# LM471.net
KiCad netlist of a schematic drawn in EasyEDA
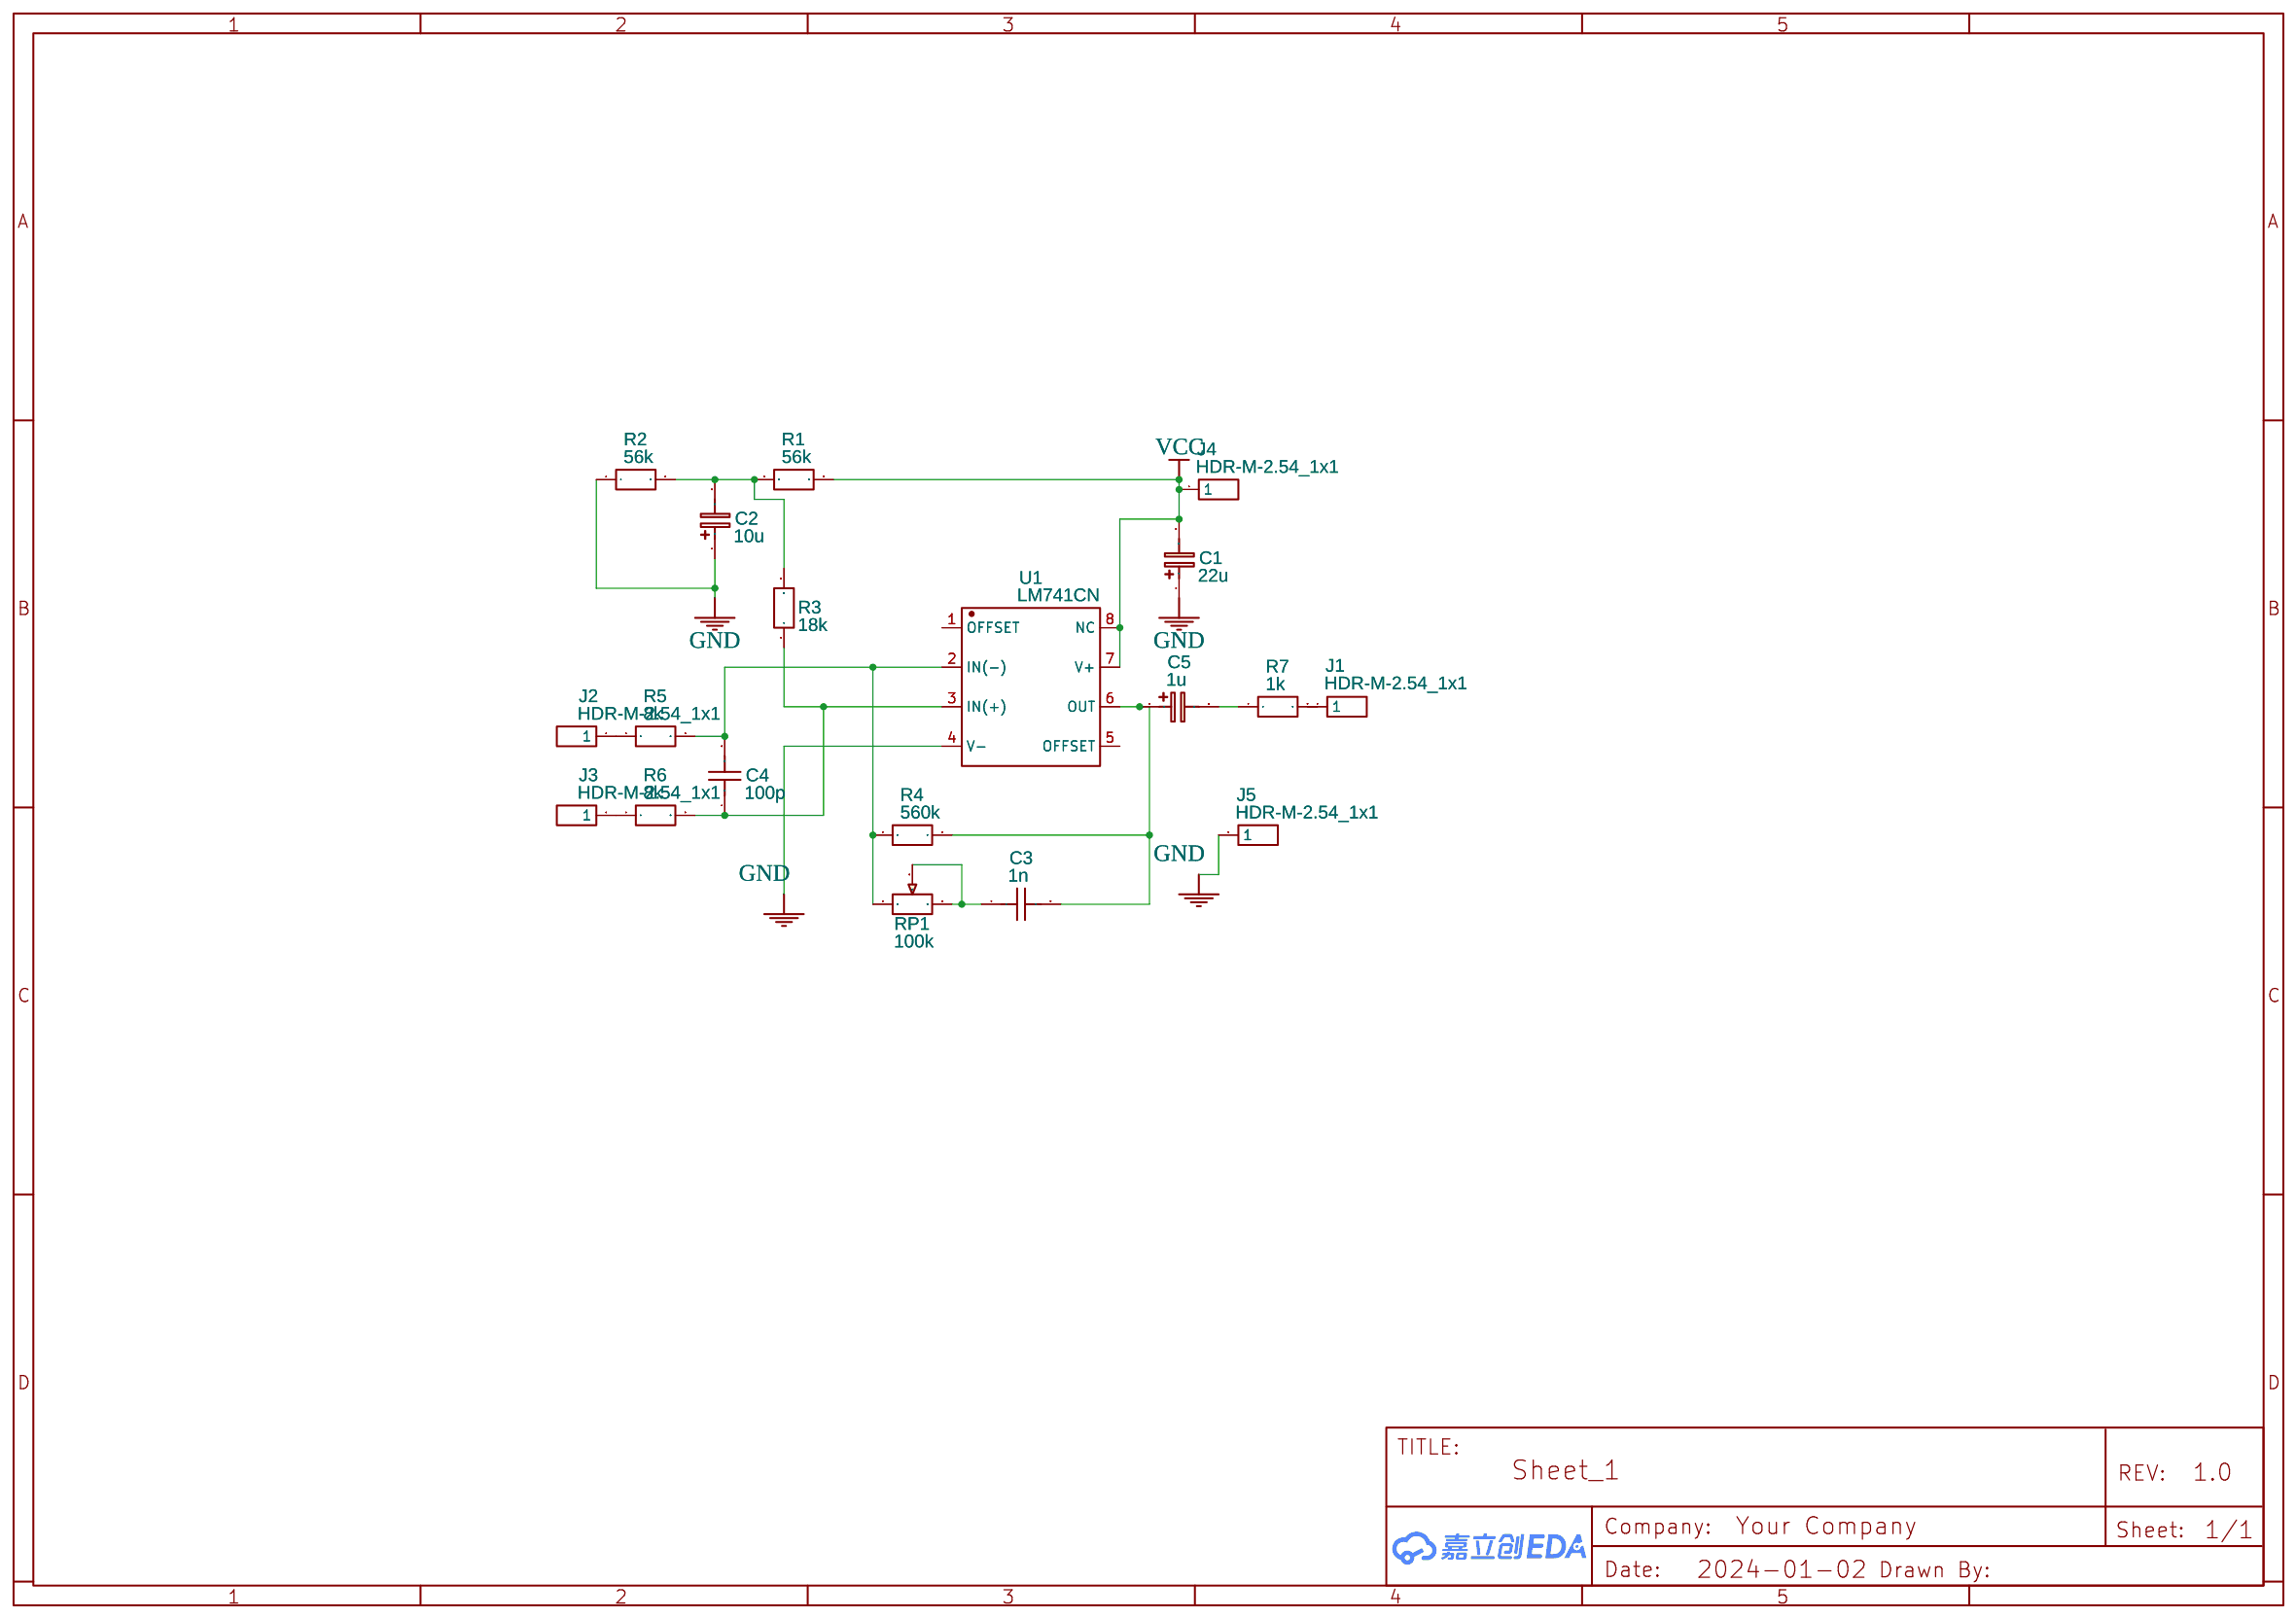
[diagram p0: schematic sheet]

(export (version "E")
  (design (tool "Eeschema 10.0.6"))
  (components
    (comp (ref "C1") (value "22u") (libsource (lib "") (part "C_Tan_SMD_A_EU_2")))
    (comp (ref "C2") (value "10u") (libsource (lib "") (part "C_Tan_SMD_A_EU_1")))
    (comp (ref "C3") (value "1n") (libsource (lib "") (part "C_0603_US")))
    (comp (ref "C4") (value "100p") (libsource (lib "") (part "C_0603_US_1")))
    (comp (ref "C5") (value "1u") (libsource (lib "") (part "C_Tan_SMD_A_EU")))
    (comp (ref "J1")
      (value "HDR-M-2.54_1x1")
      (fields (field (name "BOM_Supplier Part") "C81276"))
      (libsource (lib "") (part "HDR-M-2.54_1x1_1"))
    )
    (comp (ref "J2")
      (value "HDR-M-2.54_1x1")
      (fields (field (name "BOM_Supplier Part") "C81276"))
      (libsource (lib "") (part "HDR-M-2.54_1x1"))
    )
    (comp (ref "J3")
      (value "HDR-M-2.54_1x1")
      (fields (field (name "BOM_Supplier Part") "C81276"))
      (libsource (lib "") (part "HDR-M-2.54_1x1"))
    )
    (comp (ref "J4")
      (value "HDR-M-2.54_1x1")
      (fields (field (name "BOM_Supplier Part") "C81276"))
      (libsource (lib "") (part "HDR-M-2.54_1x1_1"))
    )
    (comp (ref "J5")
      (value "HDR-M-2.54_1x1")
      (fields (field (name "BOM_Supplier Part") "C81276"))
      (libsource (lib "") (part "HDR-M-2.54_1x1_1"))
    )
    (comp (ref "R1") (value "56k") (libsource (lib "") (part "R_0603_EU")))
    (comp (ref "R2") (value "56k") (libsource (lib "") (part "R_0603_EU")))
    (comp (ref "R3") (value "18k") (libsource (lib "") (part "R_0603_EU_1")))
    (comp (ref "R4") (value "560k") (libsource (lib "") (part "R_0603_EU")))
    (comp (ref "R5") (value "8k") (libsource (lib "") (part "R_0603_EU")))
    (comp (ref "R6") (value "8k") (libsource (lib "") (part "R_0603_EU")))
    (comp (ref "R7") (value "1k") (libsource (lib "") (part "R_0603_EU")))
    (comp (ref "RP1") (value "100k") (libsource (lib "") (part "R_3296W_EU")))
    (comp (ref "U1")
      (value "LM741CN")
      (fields (field (name "Manufacturer Part") "LM741CN/NOPB") (field (name "Manufacturer") "TI(德州仪器)"))
      (libsource (lib "") (part "LM741CN"))
    )
  )
  (nets
    (net (code "1") (name "GND") (class "Default")
      (node (ref "C1") (pin "1") (pinfunction "1_1") (pintype "unspecified"))
      (node (ref "C2") (pin "1") (pinfunction "1_1") (pintype "unspecified"))
      (node (ref "J5") (pin "1") (pinfunction "1_1") (pintype "input"))
      (node (ref "R2") (pin "1") (pinfunction "1_1") (pintype "unspecified"))
      (node (ref "U1") (pin "4") (pinfunction "V-_4") (pintype "unspecified"))
    )
    (net (code "2") (name "Net-(C2-Pad2)") (class "Default")
      (node (ref "C2") (pin "2") (pinfunction "2_2") (pintype "unspecified"))
      (node (ref "R1") (pin "1") (pinfunction "1_1") (pintype "unspecified"))
      (node (ref "R2") (pin "2") (pinfunction "2_2") (pintype "unspecified"))
      (node (ref "R3") (pin "2") (pinfunction "2_2") (pintype "unspecified"))
    )
    (net (code "3") (name "Net-(C3-Pad1)") (class "Default")
      (node (ref "C3") (pin "1") (pinfunction "1_1") (pintype "unspecified"))
      (node (ref "RP1") (pin "2") (pinfunction "2_2") (pintype "input"))
      (node (ref "RP1") (pin "3") (pinfunction "3_3") (pintype "input"))
    )
    (net (code "4") (name "Net-(C5-Pad2)") (class "Default")
      (node (ref "C5") (pin "2") (pinfunction "2_2") (pintype "unspecified"))
      (node (ref "R7") (pin "1") (pinfunction "1_1") (pintype "unspecified"))
    )
    (net (code "5") (name "Net-(J2-Pad1)") (class "Default")
      (node (ref "J2") (pin "1") (pinfunction "1_1") (pintype "input"))
      (node (ref "R5") (pin "1") (pinfunction "1_1") (pintype "unspecified"))
    )
    (net (code "6") (name "Net-(J3-Pad1)") (class "Default")
      (node (ref "J3") (pin "1") (pinfunction "1_1") (pintype "input"))
      (node (ref "R6") (pin "1") (pinfunction "1_1") (pintype "unspecified"))
    )
    (net (code "7") (name "Net-(U1-IN(+))") (class "Default")
      (node (ref "C4") (pin "1") (pinfunction "1_1") (pintype "unspecified"))
      (node (ref "R3") (pin "1") (pinfunction "1_1") (pintype "unspecified"))
      (node (ref "R6") (pin "2") (pinfunction "2_2") (pintype "unspecified"))
      (node (ref "U1") (pin "3") (pinfunction "IN(+)_3") (pintype "unspecified"))
    )
    (net (code "8") (name "Net-(U1-IN(-))") (class "Default")
      (node (ref "C4") (pin "2") (pinfunction "2_2") (pintype "unspecified"))
      (node (ref "R4") (pin "1") (pinfunction "1_1") (pintype "unspecified"))
      (node (ref "R5") (pin "2") (pinfunction "2_2") (pintype "unspecified"))
      (node (ref "RP1") (pin "1") (pinfunction "1_1") (pintype "input"))
      (node (ref "U1") (pin "2") (pinfunction "IN(-)_2") (pintype "unspecified"))
    )
    (net (code "9") (name "Net-(U1-OUT)") (class "Default")
      (node (ref "C3") (pin "2") (pinfunction "2_2") (pintype "unspecified"))
      (node (ref "C5") (pin "1") (pinfunction "1_1") (pintype "unspecified"))
      (node (ref "R4") (pin "2") (pinfunction "2_2") (pintype "unspecified"))
      (node (ref "U1") (pin "6") (pinfunction "OUT_6") (pintype "unspecified"))
    )
    (net (code "10") (name "VCC") (class "Default")
      (node (ref "C1") (pin "2") (pinfunction "2_2") (pintype "unspecified"))
      (node (ref "J4") (pin "1") (pinfunction "1_1") (pintype "input"))
      (node (ref "R1") (pin "2") (pinfunction "2_2") (pintype "unspecified"))
      (node (ref "U1") (pin "7") (pinfunction "V+_7") (pintype "unspecified"))
      (node (ref "U1") (pin "8") (pinfunction "NC_8") (pintype "unspecified"))
    )
    (net (code "11") (name "unconnected-(J1-Pad1)") (class "Default")
      (node (ref "J1") (pin "1") (pinfunction "1_1") (pintype "input"))
    )
    (net (code "12") (name "unconnected-(R7-Pad2)") (class "Default")
      (node (ref "R7") (pin "2") (pinfunction "2_2") (pintype "unspecified"))
    )
    (net (code "13") (name "unconnected-(U1-OFFSET-Pad1)") (class "Default")
      (node (ref "U1") (pin "1") (pinfunction "OFFSET_1") (pintype "unspecified"))
    )
    (net (code "14") (name "unconnected-(U1-OFFSET-Pad5)") (class "Default")
      (node (ref "U1") (pin "5") (pinfunction "OFFSET_5") (pintype "unspecified"))
    )
  )
)
